# pmon_5v.net
KiCad netlist of a schematic drawn in EAGLE
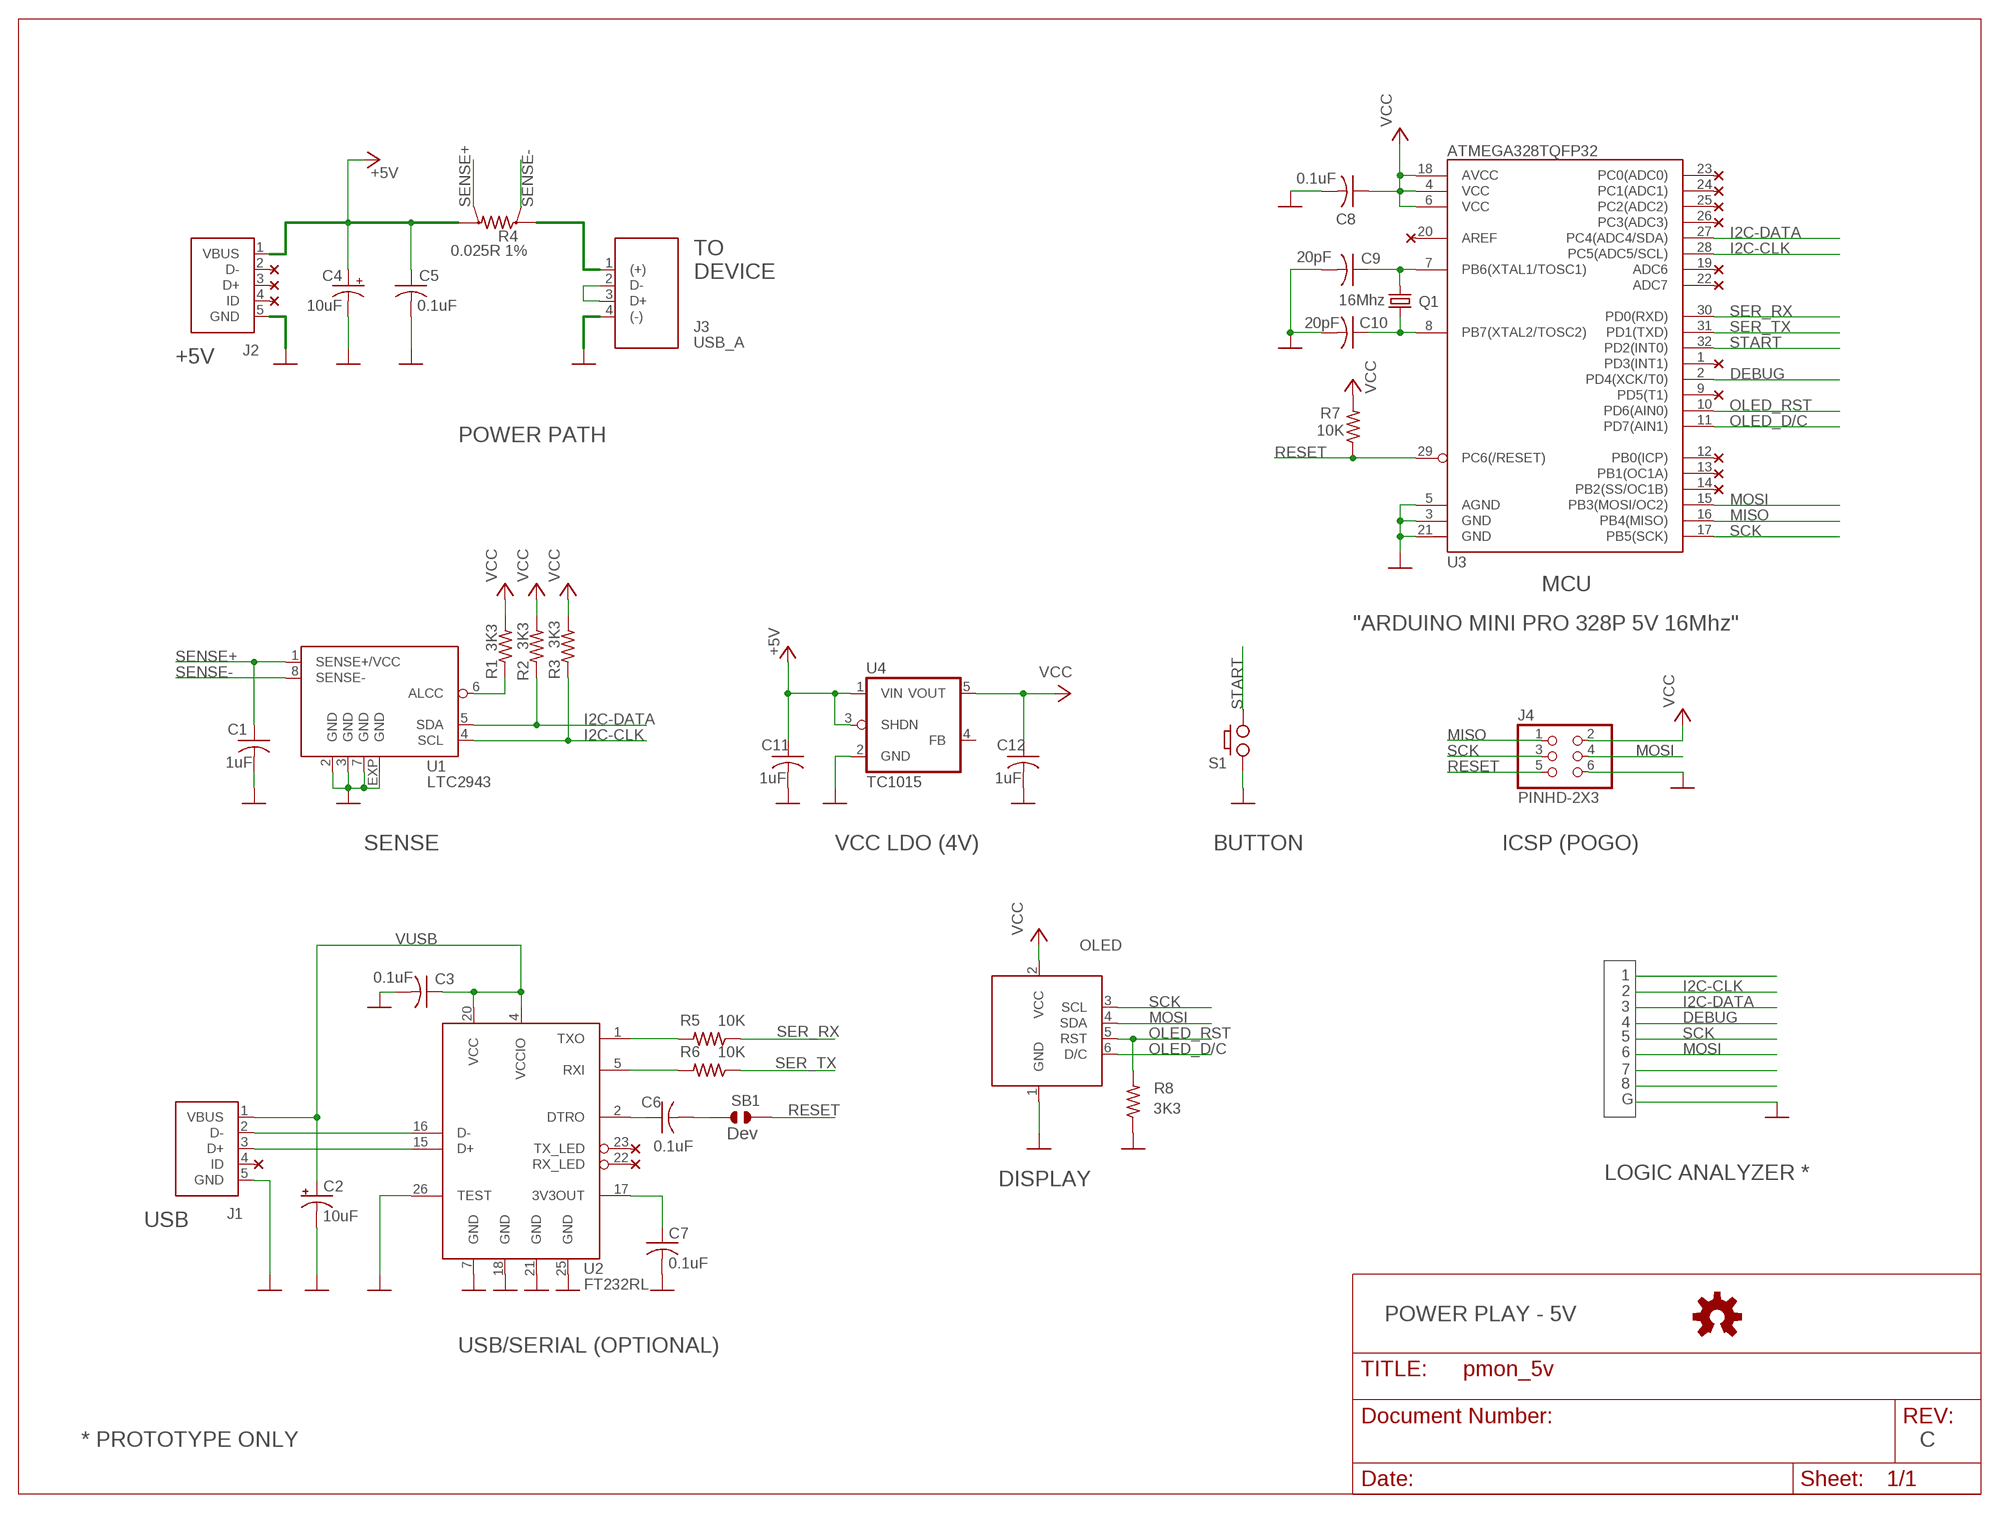
[diagram p0: schematic, sheet 1]

(export (version "E")
  (design (tool "Eeschema 10.0.6"))
  (components
    (comp (ref "C1")
      (value "1uF")
      (footprint "eagle-import:C0603")
      (libsource (lib "eagle-import") (part "CAP-C0603"))
    )
    (comp (ref "C2")
      (value "10uF")
      (footprint "eagle-import:A_3216-18R")
      (libsource (lib "eagle-import") (part "CPOL-USA/3216-18R"))
    )
    (comp (ref "C3")
      (value "0.1uF")
      (footprint "eagle-import:C0603")
      (libsource (lib "eagle-import") (part "CAP-C0603"))
    )
    (comp (ref "C4")
      (value "10uF")
      (footprint "eagle-import:A_3216-18R")
      (libsource (lib "eagle-import") (part "CPOL-USA/3216-18R"))
    )
    (comp (ref "C5")
      (value "0.1uF")
      (footprint "eagle-import:C0603")
      (libsource (lib "eagle-import") (part "CAP-C0603"))
    )
    (comp (ref "C6")
      (value "0.1uF")
      (footprint "eagle-import:C0603")
      (libsource (lib "eagle-import") (part "CAP-C0603"))
    )
    (comp (ref "C7")
      (value "0.1uF")
      (footprint "eagle-import:C0603")
      (libsource (lib "eagle-import") (part "CAP-C0603"))
    )
    (comp (ref "C8")
      (value "0.1uF")
      (footprint "eagle-import:C0603")
      (libsource (lib "eagle-import") (part "CAP-C0603"))
    )
    (comp (ref "C9")
      (value "20pF")
      (footprint "eagle-import:C0603")
      (libsource (lib "eagle-import") (part "CAP-C0603"))
    )
    (comp (ref "C10")
      (value "20pF")
      (footprint "eagle-import:C0603")
      (libsource (lib "eagle-import") (part "CAP-C0603"))
    )
    (comp (ref "C11")
      (value "1uF")
      (footprint "eagle-import:C0603")
      (libsource (lib "eagle-import") (part "CAP-C0603"))
    )
    (comp (ref "C12")
      (value "1uF")
      (footprint "eagle-import:C0603")
      (libsource (lib "eagle-import") (part "CAP-C0603"))
    )
    (comp (ref "J1")
      (value "USB")
      (footprint "eagle-import:USB-MICRO-ZX62RD-AB-5P8")
      (libsource (lib "eagle-import") (part "USB"))
    )
    (comp (ref "J2")
      (value "USB")
      (footprint "eagle-import:USB-MICRO-ZX62RD-AB-5P8")
      (libsource (lib "eagle-import") (part "USB"))
    )
    (comp (ref "J3")
      (value "USB_A")
      (footprint "eagle-import:USB_A")
      (libsource (lib "eagle-import") (part "USB_A"))
    )
    (comp (ref "J4")
      (value "PINHD-2X3")
      (footprint "eagle-import:2X03")
      (libsource (lib "eagle-import") (part "PINHD-2X3"))
    )
    (comp (ref "OLED")
      (value "OLED")
      (footprint "eagle-import:OLED")
      (libsource (lib "eagle-import") (part "OLED"))
    )
    (comp (ref "Q1")
      (value "16Mhz")
      (footprint "eagle-import:CRYSTAL-CTS406")
      (libsource (lib "eagle-import") (part "CRYSTALCTS406"))
    )
    (comp (ref "R1")
      (value "3K3")
      (footprint "eagle-import:R0603")
      (libsource (lib "eagle-import") (part "RES-R0603"))
    )
    (comp (ref "R2")
      (value "3K3")
      (footprint "eagle-import:R0603")
      (libsource (lib "eagle-import") (part "RES-R0603"))
    )
    (comp (ref "R3")
      (value "3K3")
      (footprint "eagle-import:R0603")
      (libsource (lib "eagle-import") (part "RES-R0603"))
    )
    (comp (ref "R4")
      (value "0.025R 1%")
      (footprint "eagle-import:KELVIN-6432")
      (libsource (lib "eagle-import") (part "RES-SHUNT-6432"))
    )
    (comp (ref "R5")
      (value "10K")
      (footprint "eagle-import:R0603")
      (libsource (lib "eagle-import") (part "RES-R0603"))
    )
    (comp (ref "R6")
      (value "10K")
      (footprint "eagle-import:R0603")
      (libsource (lib "eagle-import") (part "RES-R0603"))
    )
    (comp (ref "R7")
      (value "10K")
      (footprint "eagle-import:R0603")
      (libsource (lib "eagle-import") (part "RES-R0603"))
    )
    (comp (ref "R8")
      (value "3K3")
      (footprint "eagle-import:R0603")
      (libsource (lib "eagle-import") (part "RES-R0603"))
    )
    (comp (ref "S1")
      (value "PUSH_BUTTON")
      (footprint "eagle-import:TLE1105")
      (libsource (lib "eagle-import") (part "PUSH_BUTTON"))
    )
    (comp (ref "SB1")
      (value "JUMPER_SOLDER_1X2")
      (footprint "eagle-import:JUMPER_SOLDER_1X2")
      (libsource (lib "eagle-import") (part "JUMPER_SOLDER_1X2"))
    )
    (comp (ref "U$28")
      (value "OSH")
      (footprint "eagle-import:OSH")
      (libsource (lib "eagle-import") (part "OSH"))
    )
    (comp (ref "U1")
      (value "LTC2943")
      (footprint "eagle-import:DFN8-3X3")
      (libsource (lib "eagle-import") (part "LTC2943"))
    )
    (comp (ref "U2")
      (value "FT232RL")
      (footprint "eagle-import:SSOP28DB")
      (libsource (lib "eagle-import") (part "FT232RL"))
    )
    (comp (ref "U3")
      (value "ATMEGA328TQFP32")
      (footprint "eagle-import:TQFP32-08")
      (libsource (lib "eagle-import") (part "ATMEGA328TQFP32"))
    )
    (comp (ref "U4")
      (value "TC1015")
      (footprint "eagle-import:SOT25")
      (libsource (lib "eagle-import") (part "TC1015"))
    )
  )
  (nets
    (net (code "1") (name "+5V") (class "Default")
      (node (ref "C11") (pin "1") (pinfunction "1_1") (pintype "passive"))
      (node (ref "C4") (pin "+") (pinfunction "+_+") (pintype "passive"))
      (node (ref "C5") (pin "1") (pinfunction "1_1") (pintype "passive"))
      (node (ref "J2") (pin "1") (pinfunction "VBUS_1") (pintype "bidirectional"))
      (node (ref "R4") (pin "I2") (pinfunction "I2_I2") (pintype "passive"))
      (node (ref "U4") (pin "1") (pinfunction "VIN_1") (pintype "power_in"))
      (node (ref "U4") (pin "3") (pinfunction "SHDN_3") (pintype "input"))
    )
    (net (code "2") (name "/AREF") (class "Default")
      (node (ref "U3") (pin "20") (pinfunction "AREF_20") (pintype "power_in"))
    )
    (net (code "3") (name "/DEBUG") (class "Default")
      (node (ref "U3") (pin "2") (pinfunction "PD4(XCK/T0)_2") (pintype "bidirectional"))
    )
    (net (code "4") (name "/I2C-CLK") (class "Default")
      (node (ref "R3") (pin "1") (pinfunction "1_1") (pintype "passive"))
      (node (ref "U1") (pin "4") (pinfunction "SCL_4") (pintype "input"))
      (node (ref "U3") (pin "28") (pinfunction "PC5(ADC5/SCL)_28") (pintype "bidirectional"))
    )
    (net (code "5") (name "/I2C-DATA") (class "Default")
      (node (ref "R2") (pin "1") (pinfunction "1_1") (pintype "passive"))
      (node (ref "U1") (pin "5") (pinfunction "SDA_5") (pintype "bidirectional"))
      (node (ref "U3") (pin "27") (pinfunction "PC4(ADC4/SDA)_27") (pintype "bidirectional"))
    )
    (net (code "6") (name "/MISO") (class "Default")
      (node (ref "J4") (pin "1") (pinfunction "1_1") (pintype "passive"))
      (node (ref "U3") (pin "16") (pinfunction "PB4(MISO)_16") (pintype "bidirectional"))
    )
    (net (code "7") (name "/MOSI") (class "Default")
      (node (ref "J4") (pin "4") (pinfunction "4_4") (pintype "passive"))
      (node (ref "OLED") (pin "4") (pinfunction "SDA_4") (pintype "input"))
      (node (ref "U3") (pin "15") (pinfunction "PB3(MOSI/OC2)_15") (pintype "bidirectional"))
    )
    (net (code "8") (name "/OLED_D{slash}C") (class "Default")
      (node (ref "OLED") (pin "6") (pinfunction "D/C_6") (pintype "input"))
      (node (ref "U3") (pin "11") (pinfunction "PD7(AIN1)_11") (pintype "bidirectional"))
    )
    (net (code "9") (name "/OLED_RST") (class "Default")
      (node (ref "OLED") (pin "5") (pinfunction "RST_5") (pintype "input"))
      (node (ref "R8") (pin "2") (pinfunction "2_2") (pintype "passive"))
      (node (ref "U3") (pin "10") (pinfunction "PD6(AIN0)_10") (pintype "bidirectional"))
    )
    (net (code "10") (name "/RESET") (class "Default")
      (node (ref "J4") (pin "5") (pinfunction "5_5") (pintype "passive"))
      (node (ref "R7") (pin "1") (pinfunction "1_1") (pintype "passive"))
      (node (ref "SB1") (pin "2") (pinfunction "2_2") (pintype "passive"))
      (node (ref "U3") (pin "29") (pinfunction "PC6(/RESET)_29") (pintype "bidirectional"))
    )
    (net (code "11") (name "/SCK") (class "Default")
      (node (ref "J4") (pin "3") (pinfunction "3_3") (pintype "passive"))
      (node (ref "OLED") (pin "3") (pinfunction "SCL_3") (pintype "input"))
      (node (ref "U3") (pin "17") (pinfunction "PB5(SCK)_17") (pintype "bidirectional"))
    )
    (net (code "12") (name "/SENSE+") (class "Default")
      (node (ref "C1") (pin "1") (pinfunction "1_1") (pintype "passive"))
      (node (ref "R4") (pin "V2") (pinfunction "V2_V2") (pintype "passive"))
      (node (ref "U1") (pin "1") (pinfunction "SENSE+/VCC_1") (pintype "passive"))
    )
    (net (code "13") (name "/SENSE-") (class "Default")
      (node (ref "R4") (pin "V1") (pinfunction "V1_V1") (pintype "passive"))
      (node (ref "U1") (pin "8") (pinfunction "SENSE-_8") (pintype "passive"))
    )
    (net (code "14") (name "/SER_RX") (class "Default")
      (node (ref "R5") (pin "1") (pinfunction "1_1") (pintype "passive"))
      (node (ref "U3") (pin "30") (pinfunction "PD0(RXD)_30") (pintype "bidirectional"))
    )
    (net (code "15") (name "/SER_TX") (class "Default")
      (node (ref "R6") (pin "1") (pinfunction "1_1") (pintype "passive"))
      (node (ref "U3") (pin "31") (pinfunction "PD1(TXD)_31") (pintype "bidirectional"))
    )
    (net (code "16") (name "/START") (class "Default")
      (node (ref "S1") (pin "B") (pinfunction "2_B") (pintype "passive"))
      (node (ref "U3") (pin "32") (pinfunction "PD2(INT0)_32") (pintype "bidirectional"))
    )
    (net (code "17") (name "/VUSB") (class "Default")
      (node (ref "C2") (pin "+") (pinfunction "+_+") (pintype "passive"))
      (node (ref "C3") (pin "1") (pinfunction "1_1") (pintype "passive"))
      (node (ref "J1") (pin "1") (pinfunction "VBUS_1") (pintype "bidirectional"))
      (node (ref "U2") (pin "20") (pinfunction "VCC_20") (pintype "power_in"))
      (node (ref "U2") (pin "4") (pinfunction "VCCIO_4") (pintype "power_in"))
    )
    (net (code "18") (name "GND") (class "Default")
      (node (ref "C1") (pin "2") (pinfunction "2_2") (pintype "passive"))
      (node (ref "C10") (pin "2") (pinfunction "2_2") (pintype "passive"))
      (node (ref "C11") (pin "2") (pinfunction "2_2") (pintype "passive"))
      (node (ref "C12") (pin "2") (pinfunction "2_2") (pintype "passive"))
      (node (ref "C2") (pin "-") (pinfunction "-_-") (pintype "passive"))
      (node (ref "C3") (pin "2") (pinfunction "2_2") (pintype "passive"))
      (node (ref "C4") (pin "-") (pinfunction "-_-") (pintype "passive"))
      (node (ref "C5") (pin "2") (pinfunction "2_2") (pintype "passive"))
      (node (ref "C7") (pin "2") (pinfunction "2_2") (pintype "passive"))
      (node (ref "C8") (pin "2") (pinfunction "2_2") (pintype "passive"))
      (node (ref "C9") (pin "2") (pinfunction "2_2") (pintype "passive"))
      (node (ref "J1") (pin "5") (pinfunction "GND_5") (pintype "bidirectional"))
      (node (ref "J2") (pin "5") (pinfunction "GND_5") (pintype "bidirectional"))
      (node (ref "J3") (pin "4") (pinfunction "(-)_4") (pintype "passive"))
      (node (ref "J4") (pin "6") (pinfunction "6_6") (pintype "passive"))
      (node (ref "OLED") (pin "1") (pinfunction "GND_1") (pintype "power_in"))
      (node (ref "R8") (pin "1") (pinfunction "1_1") (pintype "passive"))
      (node (ref "S1") (pin "A") (pinfunction "1_A") (pintype "passive"))
      (node (ref "U1") (pin "2") (pinfunction "GND_2") (pintype "power_in"))
      (node (ref "U1") (pin "3") (pinfunction "GND_3") (pintype "power_in"))
      (node (ref "U1") (pin "7") (pinfunction "GND_7") (pintype "power_in"))
      (node (ref "U1") (pin "EXP") (pinfunction "GND_EXP") (pintype "power_in"))
      (node (ref "U2") (pin "18") (pinfunction "GND_18") (pintype "power_in"))
      (node (ref "U2") (pin "21") (pinfunction "GND_21") (pintype "power_in"))
      (node (ref "U2") (pin "25") (pinfunction "GND_25") (pintype "power_in"))
      (node (ref "U2") (pin "26") (pinfunction "TEST_26") (pintype "input"))
      (node (ref "U2") (pin "7") (pinfunction "GND_7") (pintype "power_in"))
      (node (ref "U3") (pin "21") (pinfunction "GND_21") (pintype "power_in"))
      (node (ref "U3") (pin "3") (pinfunction "GND_3") (pintype "power_in"))
      (node (ref "U3") (pin "5") (pinfunction "AGND_5") (pintype "power_in"))
      (node (ref "U4") (pin "2") (pinfunction "GND_2") (pintype "power_in"))
    )
    (net (code "19") (name "Net-(C6-Pad2)") (class "Default")
      (node (ref "C6") (pin "2") (pinfunction "2_2") (pintype "passive"))
      (node (ref "SB1") (pin "1") (pinfunction "1_1") (pintype "passive"))
    )
    (net (code "20") (name "Net-(J1-D+)") (class "Default")
      (node (ref "J1") (pin "3") (pinfunction "D+_3") (pintype "bidirectional"))
      (node (ref "U2") (pin "15") (pinfunction "D+_15") (pintype "passive"))
    )
    (net (code "21") (name "Net-(J1-D-)") (class "Default")
      (node (ref "J1") (pin "2") (pinfunction "D-_2") (pintype "bidirectional"))
      (node (ref "U2") (pin "16") (pinfunction "D-_16") (pintype "passive"))
    )
    (net (code "22") (name "Net-(J3-(+))") (class "Default")
      (node (ref "J3") (pin "1") (pinfunction "(+)_1") (pintype "passive"))
      (node (ref "R4") (pin "I1") (pinfunction "I1_I1") (pintype "passive"))
    )
    (net (code "23") (name "Net-(J3-D+)") (class "Default")
      (node (ref "J3") (pin "2") (pinfunction "D-_2") (pintype "passive"))
      (node (ref "J3") (pin "3") (pinfunction "D+_3") (pintype "passive"))
    )
    (net (code "24") (name "Net-(Q1-2)") (class "Default")
      (node (ref "C10") (pin "1") (pinfunction "1_1") (pintype "passive"))
      (node (ref "Q1") (pin "3") (pinfunction "2_3") (pintype "passive"))
      (node (ref "U3") (pin "8") (pinfunction "PB7(XTAL2/TOSC2)_8") (pintype "bidirectional"))
    )
    (net (code "25") (name "Net-(U1-ALCC)") (class "Default")
      (node (ref "R1") (pin "1") (pinfunction "1_1") (pintype "passive"))
      (node (ref "U1") (pin "6") (pinfunction "ALCC_6") (pintype "open_collector"))
    )
    (net (code "26") (name "Net-(U2-3V3OUT)") (class "Default")
      (node (ref "C7") (pin "1") (pinfunction "1_1") (pintype "passive"))
      (node (ref "U2") (pin "17") (pinfunction "3V3OUT_17") (pintype "power_in"))
    )
    (net (code "27") (name "Net-(U2-DTRO)") (class "Default")
      (node (ref "C6") (pin "1") (pinfunction "1_1") (pintype "passive"))
      (node (ref "U2") (pin "2") (pinfunction "DTRO_2") (pintype "output"))
    )
    (net (code "28") (name "Net-(U2-RXI)") (class "Default")
      (node (ref "R6") (pin "2") (pinfunction "2_2") (pintype "passive"))
      (node (ref "U2") (pin "5") (pinfunction "RXI_5") (pintype "input"))
    )
    (net (code "29") (name "Net-(U2-TXO)") (class "Default")
      (node (ref "R5") (pin "2") (pinfunction "2_2") (pintype "passive"))
      (node (ref "U2") (pin "1") (pinfunction "TXO_1") (pintype "output"))
    )
    (net (code "30") (name "Net-(U3-PB6(XTAL1{slash}TOSC1))") (class "Default")
      (node (ref "C9") (pin "1") (pinfunction "1_1") (pintype "passive"))
      (node (ref "Q1") (pin "1") (pinfunction "1_1") (pintype "passive"))
      (node (ref "U3") (pin "7") (pinfunction "PB6(XTAL1/TOSC1)_7") (pintype "bidirectional"))
    )
    (net (code "31") (name "VCC") (class "Default")
      (node (ref "C12") (pin "1") (pinfunction "1_1") (pintype "passive"))
      (node (ref "C8") (pin "1") (pinfunction "1_1") (pintype "passive"))
      (node (ref "J4") (pin "2") (pinfunction "2_2") (pintype "passive"))
      (node (ref "OLED") (pin "2") (pinfunction "VCC_2") (pintype "power_in"))
      (node (ref "R1") (pin "2") (pinfunction "2_2") (pintype "passive"))
      (node (ref "R2") (pin "2") (pinfunction "2_2") (pintype "passive"))
      (node (ref "R3") (pin "2") (pinfunction "2_2") (pintype "passive"))
      (node (ref "R7") (pin "2") (pinfunction "2_2") (pintype "passive"))
      (node (ref "U3") (pin "18") (pinfunction "AVCC_18") (pintype "power_in"))
      (node (ref "U3") (pin "4") (pinfunction "VCC_4") (pintype "power_in"))
      (node (ref "U3") (pin "6") (pinfunction "VCC_6") (pintype "power_in"))
      (node (ref "U4") (pin "5") (pinfunction "VOUT_5") (pintype "power_in"))
    )
    (net (code "32") (name "unconnected-(J1-ID-Pad4)") (class "Default")
      (node (ref "J1") (pin "4") (pinfunction "ID_4") (pintype "bidirectional"))
    )
    (net (code "33") (name "unconnected-(J2-D+-Pad3)") (class "Default")
      (node (ref "J2") (pin "3") (pinfunction "D+_3") (pintype "bidirectional"))
    )
    (net (code "34") (name "unconnected-(J2-D--Pad2)") (class "Default")
      (node (ref "J2") (pin "2") (pinfunction "D-_2") (pintype "bidirectional"))
    )
    (net (code "35") (name "unconnected-(J2-ID-Pad4)") (class "Default")
      (node (ref "J2") (pin "4") (pinfunction "ID_4") (pintype "bidirectional"))
    )
    (net (code "36") (name "unconnected-(U2-RX_LED-Pad22)") (class "Default")
      (node (ref "U2") (pin "22") (pinfunction "RX_LED_22") (pintype "output"))
    )
    (net (code "37") (name "unconnected-(U2-TX_LED-Pad23)") (class "Default")
      (node (ref "U2") (pin "23") (pinfunction "TX_LED_23") (pintype "output"))
    )
    (net (code "38") (name "unconnected-(U3-ADC6-Pad19)") (class "Default")
      (node (ref "U3") (pin "19") (pinfunction "ADC6_19") (pintype "bidirectional"))
    )
    (net (code "39") (name "unconnected-(U3-ADC7-Pad22)") (class "Default")
      (node (ref "U3") (pin "22") (pinfunction "ADC7_22") (pintype "bidirectional"))
    )
    (net (code "40") (name "unconnected-(U3-PB0(ICP)-Pad12)") (class "Default")
      (node (ref "U3") (pin "12") (pinfunction "PB0(ICP)_12") (pintype "bidirectional"))
    )
    (net (code "41") (name "unconnected-(U3-PB1(OC1A)-Pad13)") (class "Default")
      (node (ref "U3") (pin "13") (pinfunction "PB1(OC1A)_13") (pintype "bidirectional"))
    )
    (net (code "42") (name "unconnected-(U3-PB2(SS{slash}OC1B)-Pad14)") (class "Default")
      (node (ref "U3") (pin "14") (pinfunction "PB2(SS/OC1B)_14") (pintype "bidirectional"))
    )
    (net (code "43") (name "unconnected-(U3-PC0(ADC0)-Pad23)") (class "Default")
      (node (ref "U3") (pin "23") (pinfunction "PC0(ADC0)_23") (pintype "bidirectional"))
    )
    (net (code "44") (name "unconnected-(U3-PC1(ADC1)-Pad24)") (class "Default")
      (node (ref "U3") (pin "24") (pinfunction "PC1(ADC1)_24") (pintype "bidirectional"))
    )
    (net (code "45") (name "unconnected-(U3-PC2(ADC2)-Pad25)") (class "Default")
      (node (ref "U3") (pin "25") (pinfunction "PC2(ADC2)_25") (pintype "bidirectional"))
    )
    (net (code "46") (name "unconnected-(U3-PC3(ADC3)-Pad26)") (class "Default")
      (node (ref "U3") (pin "26") (pinfunction "PC3(ADC3)_26") (pintype "bidirectional"))
    )
    (net (code "47") (name "unconnected-(U3-PD3(INT1)-Pad1)") (class "Default")
      (node (ref "U3") (pin "1") (pinfunction "PD3(INT1)_1") (pintype "bidirectional"))
    )
    (net (code "48") (name "unconnected-(U3-PD5(T1)-Pad9)") (class "Default")
      (node (ref "U3") (pin "9") (pinfunction "PD5(T1)_9") (pintype "bidirectional"))
    )
    (net (code "49") (name "unconnected-(U4-FB-Pad4)") (class "Default")
      (node (ref "U4") (pin "4") (pinfunction "FB_4") (pintype "input"))
    )
  )
)
